# Bat_20Vvoeding.net
KiCad netlist of a schematic drawn in Altium Designer
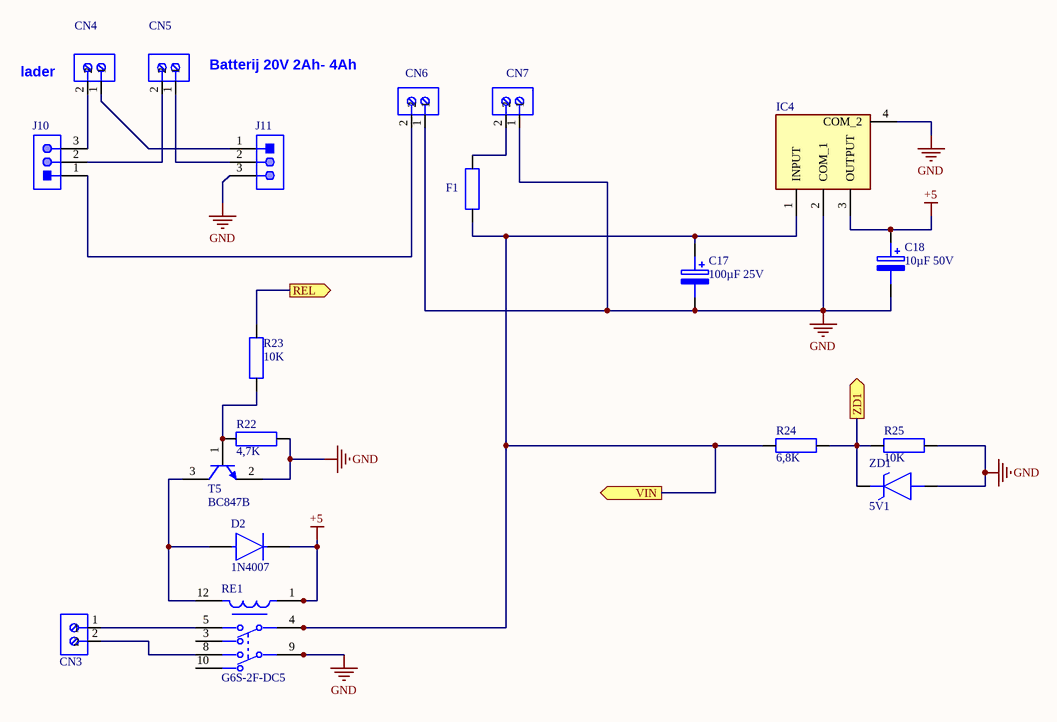
[diagram p0: Bat 20Vvoeding.SchDoc]

(export (version "E")
  (design (tool "Eeschema 10.0.6"))
  (components
    (comp (ref "C17")
      (value "100µF 25V")
      (footprint "caprad100mil")
      (description "Capacitor Polarised")
      (fields
        (field (name "MANUFACTURER_PART_NUMBER") "T494D227K006AT")
        (field (name "MOUSER PART NUMBER") "80-T494D227K006")
      )
      (libsource (lib "Schlib1") (part "ELCO220uF"))
    )
    (comp (ref "C18")
      (value "10µF 50V")
      (footprint "caprad100mil")
      (description "Capacitor Polarised")
      (fields
        (field (name "MANUFACTURER_PART_NUMBER") "T494D227K006AT")
        (field (name "MOUSER PART NUMBER") "80-T494D227K006")
      )
      (libsource (lib "Schlib1") (part "ELCO220uF"))
    )
    (comp (ref "CN3")
      (value "282836-2")
      (footprint "cnn2pin")
      (description "Female Header, Pitch 5 mm, 1 x 2 Position, Height 10 mm, Tail Length 3.5 mm, Rohs, Bulk")
      (fields (field (name "VOLTAGE") "300V") (field (name "MANUFACTURER") "TE Connectivity"))
      (libsource (lib "soldeerstation") (part "CNN2P"))
    )
    (comp (ref "CN4")
      (value "282836-2")
      (footprint "cnn2pin")
      (description "Female Header, Pitch 5 mm, 1 x 2 Position, Height 10 mm, Tail Length 3.5 mm, Rohs, Bulk")
      (fields (field (name "VOLTAGE") "300V") (field (name "MANUFACTURER") "TE Connectivity"))
      (libsource (lib "soldeerstation") (part "CNN2P"))
    )
    (comp (ref "CN5")
      (value "282836-2")
      (footprint "cnn2pin")
      (description "Female Header, Pitch 5 mm, 1 x 2 Position, Height 10 mm, Tail Length 3.5 mm, Rohs, Bulk")
      (fields (field (name "VOLTAGE") "300V") (field (name "MANUFACTURER") "TE Connectivity"))
      (libsource (lib "soldeerstation") (part "CNN2P"))
    )
    (comp (ref "CN6")
      (value "282836-2")
      (footprint "cnn2pin")
      (description "Female Header, Pitch 5 mm, 1 x 2 Position, Height 10 mm, Tail Length 3.5 mm, Rohs, Bulk")
      (fields (field (name "VOLTAGE") "300V") (field (name "MANUFACTURER") "TE Connectivity"))
      (libsource (lib "soldeerstation") (part "CNN2P"))
    )
    (comp (ref "CN7")
      (value "282836-2")
      (footprint "cnn2pin")
      (description "Female Header, Pitch 5 mm, 1 x 2 Position, Height 10 mm, Tail Length 3.5 mm, Rohs, Bulk")
      (fields (field (name "VOLTAGE") "300V") (field (name "MANUFACTURER") "TE Connectivity"))
      (libsource (lib "soldeerstation") (part "CNN2P"))
    )
    (comp (ref "D2")
      (value "1N4007")
      (footprint "FP-1N4007-MFG")
      (description "Rectifier diode 1000 V 1 A DO-41, ,")
      (fields
        (field (name "MANUFACTURER") "Diotec")
        (field (name "OCTOPART") "https://octopart.com/1n4007-diotec-4040411")
      )
      (libsource (lib "Altium Content Vault") (part "d7152d700b627762746794eb795d46e"))
    )
    (comp (ref "F1")
      (value "4,7K")
      (footprint "Fuze")
      (description "Resistor")
      (fields (field (name "MANUFACTURER_PART_NUMBER") "CPF0201D10K2C1"))
      (libsource (lib "soldeerstation") (part "Fuze"))
    )
    (comp (ref "IC4")
      (value "TL780-05CKTTR")
      (footprint "SamacSys:TL78005CKTTR")
      (description "Integrated Circuit")
      (libsource (lib "soldeerstation") (part "TL780-05CKTTR"))
    )
    (comp (ref "J10")
      (value "~")
      (footprint "3pinsheader")
      (description "THT Vertical Pin Header WR-PHD, Pitch 2.54 mm, Single Row, 2 pins")
      (fields
        (field (name "MANUFACTURER") "Wurth Elektronik")
        (field (name "PART NUMBER") "61300211121")
        (field (name "PUBLISHER") "WurthElektronik")
      )
      (libsource (lib "Soldeerstation_1") (part "header3pin"))
    )
    (comp (ref "J11")
      (value "~")
      (footprint "3pinsheader")
      (description "THT Vertical Pin Header WR-PHD, Pitch 2.54 mm, Single Row, 2 pins")
      (fields
        (field (name "MANUFACTURER") "Wurth Elektronik")
        (field (name "PART NUMBER") "61300211121")
        (field (name "PUBLISHER") "WurthElektronik")
      )
      (libsource (lib "") (part "header3pin_1"))
    )
    (comp (ref "R22")
      (value "4,7K")
      (footprint "res0805ph")
      (description "Resistor")
      (fields (field (name "MANUFACTURER_PART_NUMBER") "CPF0201D10K2C1"))
      (libsource (lib "soldeerstation") (part "Res"))
    )
    (comp (ref "R23")
      (value "10K")
      (footprint "res0805ph")
      (description "Resistor")
      (fields (field (name "MANUFACTURER_PART_NUMBER") "CPF0201D10K2C1"))
      (libsource (lib "") (part "Res_1"))
    )
    (comp (ref "R24")
      (value "6,8K")
      (footprint "res0805ph")
      (description "Resistor")
      (fields (field (name "MANUFACTURER_PART_NUMBER") "CPF0201D10K2C1"))
      (libsource (lib "soldeerstation") (part "Res"))
    )
    (comp (ref "R25")
      (value "10K")
      (footprint "res0805ph")
      (description "Resistor")
      (fields (field (name "MANUFACTURER_PART_NUMBER") "CPF0201D10K2C1"))
      (libsource (lib "") (part "Res_2"))
    )
    (comp (ref "RE1")
      (value "G6S-2F-DC5")
      (footprint "FP-G6S-2F-DC5-MFG")
      (description "RELAY TELECOM DPDT 2A 5VDC")
      (fields
        (field (name "MANUFACTURER") "Omron")
        (field (name "OCTOPART") "https://octopart.com/g6s-2f-dc5-omron-85236")
      )
      (libsource (lib "relayOmron") (part "CMP-08823-000012-1"))
    )
    (comp (ref "T5")
      (value "BC847B")
      (footprint "sot23")
      (description "NPN Silicon AF Transistor, 45 V VCEO, 100 mA IC, SOT23, Reel, Green")
      (fields (field (name "MANUFACTURER") "Infineon"))
      (libsource (lib "soldeerstation") (part "BC847"))
    )
    (comp (ref "ZD1")
      (value "5V1")
      (footprint "SamacSys:DIOAD1068W53L380D172")
      (description "Zener Diode")
      (fields
        (field (name "MANUFACTURER_PART_NUMBER") "BZX79C6V8")
        (field (name "MOUSER PART NUMBER") "512-BZX79C6V8")
      )
      (libsource (lib "Schlib1") (part "BZX79C3V3"))
    )
  )
  (nets
    (net (code "1") (name "+5") (class "Default")
      (node (ref "C18") (pin "1") (pinfunction "+_1") (pintype "passive"))
      (node (ref "D2") (pin "1") (pinfunction "C_1") (pintype "passive"))
      (node (ref "IC4") (pin "3") (pinfunction "OUTPUT_3") (pintype "passive"))
      (node (ref "RE1") (pin "1") (pinfunction "1_1") (pintype "passive"))
    )
    (net (code "2") (name "/REL") (class "Default")
      (node (ref "R23") (pin "2") (pinfunction "2_2") (pintype "passive"))
    )
    (net (code "3") (name "/VIN") (class "Default")
      (node (ref "C17") (pin "1") (pinfunction "+_1") (pintype "passive"))
      (node (ref "F1") (pin "1") (pinfunction "1_1") (pintype "passive"))
      (node (ref "IC4") (pin "1") (pinfunction "INPUT_1") (pintype "passive"))
      (node (ref "R24") (pin "1") (pinfunction "1_1") (pintype "passive"))
      (node (ref "RE1") (pin "4") (pinfunction "4_4") (pintype "passive"))
    )
    (net (code "4") (name "/ZD1") (class "Default")
      (node (ref "R24") (pin "2") (pinfunction "2_2") (pintype "passive"))
      (node (ref "R25") (pin "2") (pinfunction "2_2") (pintype "passive"))
      (node (ref "ZD1") (pin "1") (pinfunction "K_1") (pintype "passive"))
    )
    (net (code "5") (name "GND") (class "Default")
      (node (ref "C17") (pin "2") (pinfunction "-_2") (pintype "passive"))
      (node (ref "C18") (pin "2") (pinfunction "-_2") (pintype "passive"))
      (node (ref "CN6") (pin "1") (pinfunction "1_1") (pintype "passive"))
      (node (ref "CN7") (pin "1") (pinfunction "1_1") (pintype "passive"))
      (node (ref "IC4") (pin "2") (pinfunction "COM_1_2") (pintype "passive"))
      (node (ref "IC4") (pin "4") (pinfunction "COM_2_4") (pintype "passive"))
      (node (ref "J11") (pin "3") (pinfunction "3_3") (pintype "passive"))
      (node (ref "R22") (pin "2") (pinfunction "2_2") (pintype "passive"))
      (node (ref "R25") (pin "1") (pinfunction "1_1") (pintype "passive"))
      (node (ref "RE1") (pin "9") (pinfunction "9_9") (pintype "passive"))
      (node (ref "T5") (pin "2") (pinfunction "E_2") (pintype "passive"))
      (node (ref "ZD1") (pin "2") (pinfunction "A_2") (pintype "passive"))
    )
    (net (code "6") (name "Net-(CN3-Pad1)") (class "Default")
      (node (ref "CN3") (pin "1") (pinfunction "1_1") (pintype "passive"))
      (node (ref "RE1") (pin "5") (pinfunction "5_5") (pintype "passive"))
    )
    (net (code "7") (name "Net-(CN3-Pad2)") (class "Default")
      (node (ref "CN3") (pin "2") (pinfunction "2_2") (pintype "passive"))
      (node (ref "RE1") (pin "8") (pinfunction "8_8") (pintype "passive"))
    )
    (net (code "8") (name "Net-(CN4-Pad1)") (class "Default")
      (node (ref "CN4") (pin "1") (pinfunction "1_1") (pintype "passive"))
      (node (ref "J11") (pin "1") (pinfunction "1_1") (pintype "passive"))
    )
    (net (code "9") (name "Net-(CN4-Pad2)") (class "Default")
      (node (ref "CN4") (pin "2") (pinfunction "2_2") (pintype "passive"))
      (node (ref "J10") (pin "3") (pinfunction "3_3") (pintype "passive"))
    )
    (net (code "10") (name "Net-(CN5-Pad1)") (class "Default")
      (node (ref "CN5") (pin "1") (pinfunction "1_1") (pintype "passive"))
      (node (ref "J11") (pin "2") (pinfunction "2_2") (pintype "passive"))
    )
    (net (code "11") (name "Net-(CN5-Pad2)") (class "Default")
      (node (ref "CN5") (pin "2") (pinfunction "2_2") (pintype "passive"))
      (node (ref "J10") (pin "2") (pinfunction "2_2") (pintype "passive"))
    )
    (net (code "12") (name "Net-(CN6-Pad2)") (class "Default")
      (node (ref "CN6") (pin "2") (pinfunction "2_2") (pintype "passive"))
      (node (ref "J10") (pin "1") (pinfunction "1_1") (pintype "passive"))
    )
    (net (code "13") (name "Net-(CN7-Pad2)") (class "Default")
      (node (ref "CN7") (pin "2") (pinfunction "2_2") (pintype "passive"))
      (node (ref "F1") (pin "2") (pinfunction "2_2") (pintype "passive"))
    )
    (net (code "14") (name "Net-(D2-A)") (class "Default")
      (node (ref "D2") (pin "2") (pinfunction "A_2") (pintype "passive"))
      (node (ref "RE1") (pin "12") (pinfunction "12_12") (pintype "passive"))
      (node (ref "T5") (pin "3") (pinfunction "C_3") (pintype "passive"))
    )
    (net (code "15") (name "Net-(T5-B)") (class "Default")
      (node (ref "R22") (pin "1") (pinfunction "1_1") (pintype "passive"))
      (node (ref "R23") (pin "1") (pinfunction "1_1") (pintype "passive"))
      (node (ref "T5") (pin "1") (pinfunction "B_1") (pintype "passive"))
    )
    (net (code "16") (name "unconnected-(RE1-Pad3)") (class "Default")
      (node (ref "RE1") (pin "3") (pinfunction "3_3") (pintype "passive"))
    )
    (net (code "17") (name "unconnected-(RE1-Pad10)") (class "Default")
      (node (ref "RE1") (pin "10") (pinfunction "10_10") (pintype "passive"))
    )
  )
)
